# cell.net
KiCad netlist of a schematic drawn in EAGLE
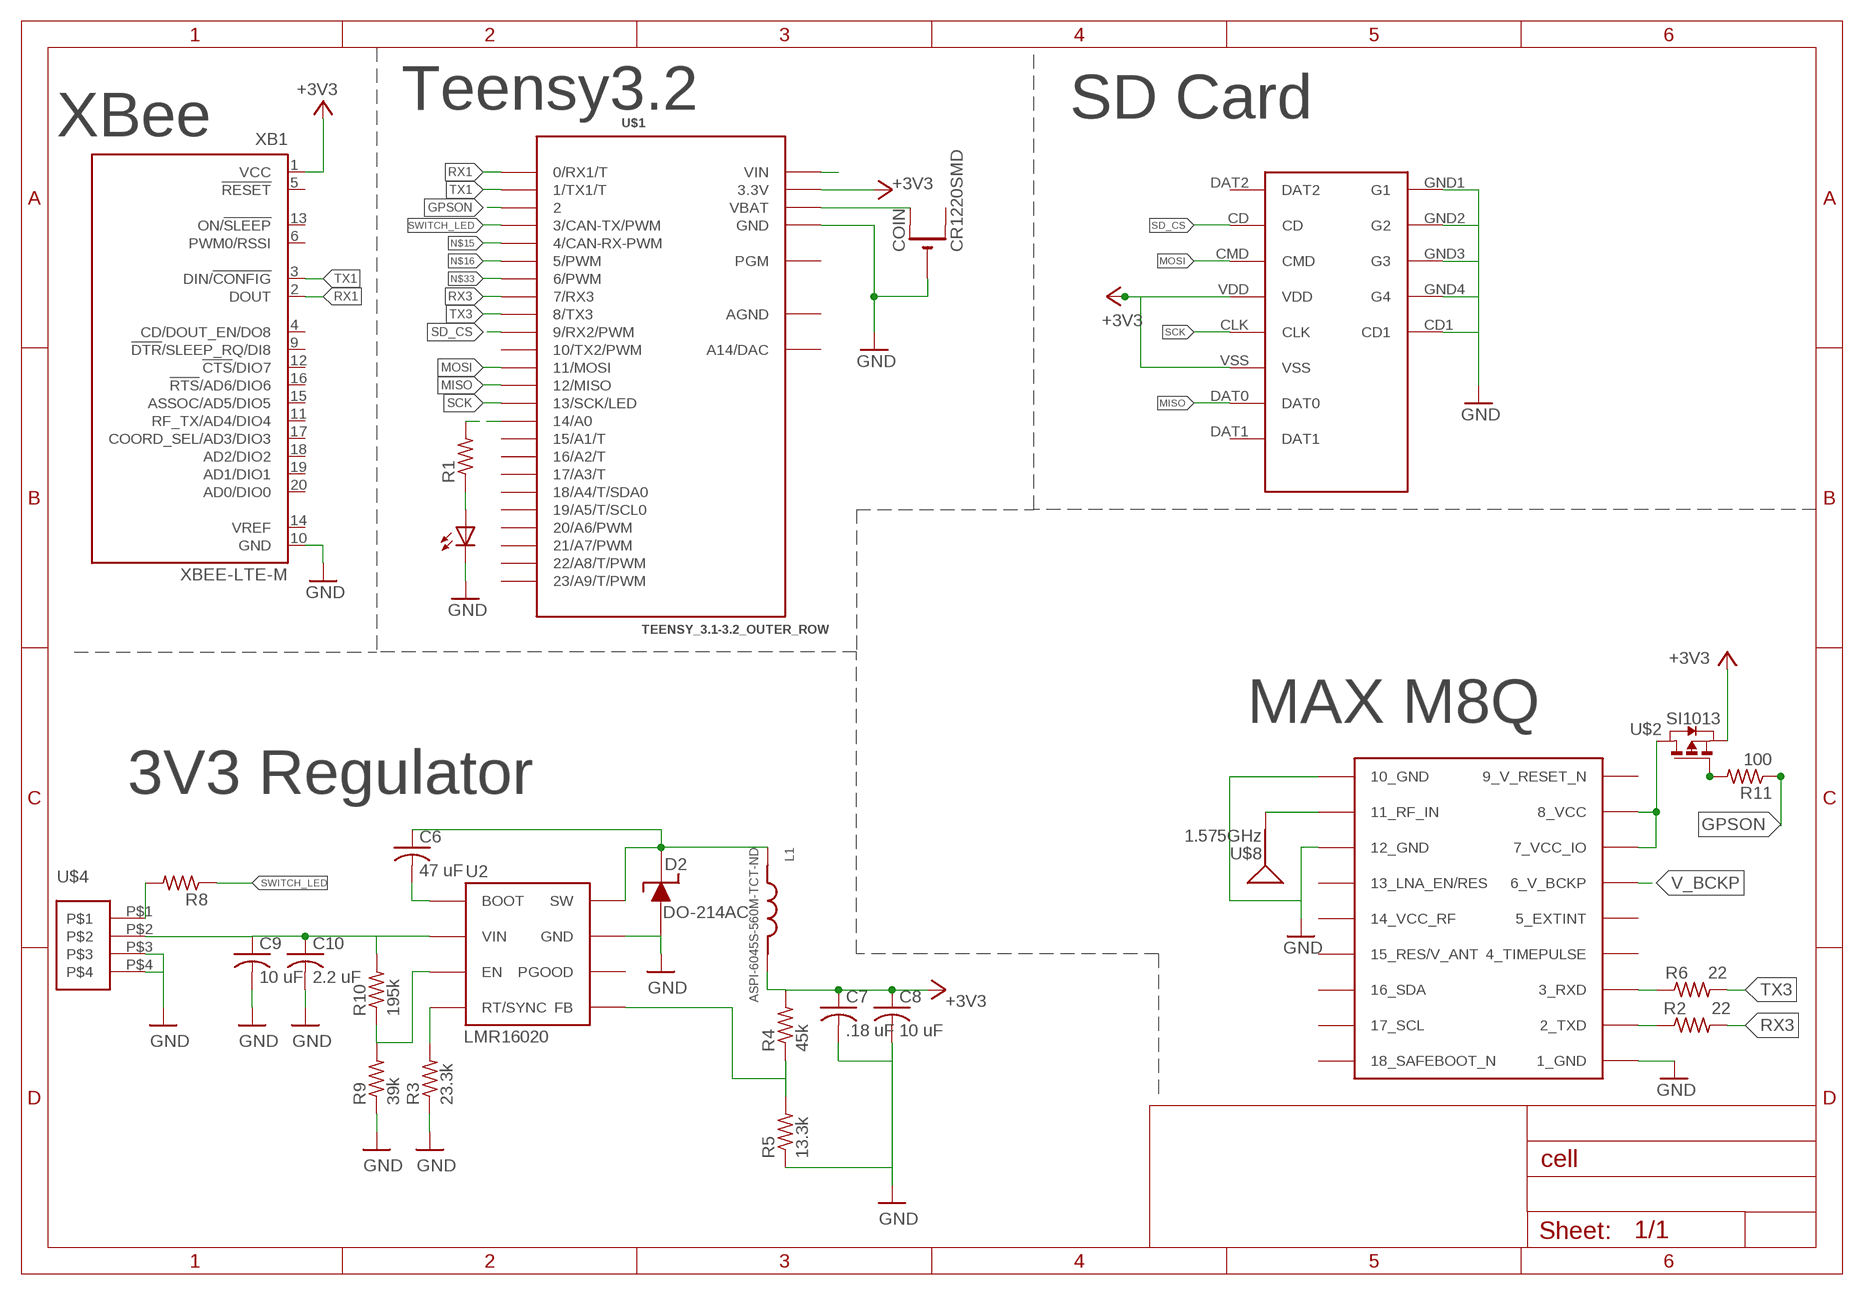
[diagram p0: schematic, sheet 1]

(export (version "E")
  (design (tool "Eeschema 10.0.6"))
  (components
    (comp (ref "C6")
      (value "47 uF")
      (footprint "eagle-import:C0805")
      (libsource (lib "eagle-import") (part "C-USC0805"))
    )
    (comp (ref "C7")
      (value ".18 uF")
      (footprint "eagle-import:C0603")
      (libsource (lib "eagle-import") (part "C-USC0603"))
    )
    (comp (ref "C8")
      (value "10 uF")
      (footprint "eagle-import:C0603")
      (libsource (lib "eagle-import") (part "C-USC0603"))
    )
    (comp (ref "C9")
      (value "10 uF")
      (footprint "eagle-import:C1210")
      (libsource (lib "eagle-import") (part "C-USC1210"))
    )
    (comp (ref "C10")
      (value "2.2 uF")
      (footprint "eagle-import:C1210")
      (libsource (lib "eagle-import") (part "C-USC1210"))
    )
    (comp (ref "COIN")
      (value "CR1220SMD")
      (footprint "eagle-import:CR1220-SMD")
      (libsource (lib "eagle-import") (part "CR1220SMT"))
    )
    (comp (ref "D2")
      (value "DO-214AC")
      (footprint "eagle-import:DO-214AC")
      (libsource (lib "eagle-import") (part "DO-214AC"))
    )
    (comp (ref "L1")
      (value "ASPI-6045S-560M-TCT-ND")
      (footprint "eagle-import:ABRACON")
      (libsource (lib "eagle-import") (part "ASPI-6045S-560M-TCT-ND"))
    )
    (comp (ref "LED1")
      (value "Green")
      (footprint "eagle-import:CHIP-LED0603")
      (libsource (lib "eagle-import") (part "LEDCHIP-LED0603"))
    )
    (comp (ref "R1")
      (value "470")
      (footprint "eagle-import:R0603")
      (libsource (lib "eagle-import") (part "resistor_R-US_R0603"))
    )
    (comp (ref "R2")
      (value "22")
      (footprint "eagle-import:R0603")
      (libsource (lib "eagle-import") (part "R-US_R0603"))
    )
    (comp (ref "R3")
      (value "23.3k")
      (footprint "eagle-import:R0603")
      (libsource (lib "eagle-import") (part "resistor_R-US_R0603"))
    )
    (comp (ref "R4")
      (value "45k")
      (footprint "eagle-import:R0603")
      (libsource (lib "eagle-import") (part "resistor_R-US_R0603"))
    )
    (comp (ref "R5")
      (value "13.3k")
      (footprint "eagle-import:R0603")
      (libsource (lib "eagle-import") (part "resistor_R-US_R0603"))
    )
    (comp (ref "R6")
      (value "22")
      (footprint "eagle-import:R0603")
      (libsource (lib "eagle-import") (part "R-US_R0603"))
    )
    (comp (ref "R8")
      (value "R-US_R0603")
      (footprint "eagle-import:R0603")
      (libsource (lib "eagle-import") (part "resistor_R-US_R0603"))
    )
    (comp (ref "R9")
      (value "39k")
      (footprint "eagle-import:R0603")
      (libsource (lib "eagle-import") (part "resistor_R-US_R0603"))
    )
    (comp (ref "R10")
      (value "195k")
      (footprint "eagle-import:R0603")
      (libsource (lib "eagle-import") (part "resistor_R-US_R0603"))
    )
    (comp (ref "R11")
      (value "100")
      (footprint "eagle-import:R0603")
      (libsource (lib "eagle-import") (part "R-US_R0603"))
    )
    (comp (ref "U$1")
      (value "TEENSY_3.1-3.2_OUTER_ROW")
      (footprint "eagle-import:TEENSY_3.0-3.2&LC_OUTER_ROW")
      (libsource (lib "eagle-import") (part "TEENSY_3.1-3.2_OUTER_ROW"))
    )
    (comp (ref "U$2")
      (value "SI1013")
      (footprint "eagle-import:SC-75")
      (libsource (lib "eagle-import") (part "SI1013"))
    )
    (comp (ref "U$3")
      (value "MICRO_SD")
      (footprint "eagle-import:MICRO_SD_HINGED")
      (libsource (lib "eagle-import") (part "MICRO_SD"))
    )
    (comp (ref "U$4")
      (value "MICROCLASP_4")
      (footprint "eagle-import:4_PIN_MICROCLASP")
      (libsource (lib "eagle-import") (part "MICROCLASP_4"))
    )
    (comp (ref "U$7")
      (value "MAX-M8")
      (footprint "eagle-import:MAX-M8")
      (libsource (lib "eagle-import") (part "MAX-M8"))
    )
    (comp (ref "U$8")
      (value "1.575GHz")
      (footprint "eagle-import:SPARKFUN-GPS_ANT-GPS-2X7MM")
      (libsource (lib "eagle-import") (part "SPARKFUN-GPS_ANTENNAGPS-2X7MM"))
    )
    (comp (ref "U2")
      (value "LMR16020")
      (footprint "eagle-import:SO8")
      (libsource (lib "eagle-import") (part "LMR16020"))
    )
    (comp (ref "XB1")
      (value "XBEE-LTE-M")
      (footprint "eagle-import:XBEE-PRO")
      (fields (field (name "MPN") "XBP24-AWI-001"))
      (libsource (lib "eagle-import") (part "XBEE-PRO"))
    )
  )
  (nets
    (net (code "1") (name "+3V3") (class "Default")
      (node (ref "C7") (pin "1") (pinfunction "1_1") (pintype "passive"))
      (node (ref "C8") (pin "1") (pinfunction "1_1") (pintype "passive"))
      (node (ref "L1") (pin "P$2") (pinfunction "P$2_P$2") (pintype "bidirectional"))
      (node (ref "R4") (pin "2") (pinfunction "2_2") (pintype "passive"))
      (node (ref "U$1") (pin "3.3V") (pinfunction "3.3V_3.3V") (pintype "power_in"))
      (node (ref "U$1") (pin "3.3V1") (pinfunction "3.3V_3.3V1") (pintype "power_in"))
      (node (ref "U$2") (pin "P$2") (pinfunction "S_P$2") (pintype "passive"))
      (node (ref "U$3") (pin "VDD") (pinfunction "VDD_VDD") (pintype "bidirectional"))
      (node (ref "U$3") (pin "VSS") (pinfunction "VSS_VSS") (pintype "bidirectional"))
      (node (ref "XB1") (pin "1") (pinfunction "VCC_1") (pintype "power_in"))
    )
    (net (code "2") (name "/9_V_RESET_N") (class "Default")
      (node (ref "U$7") (pin "9_RESET_N") (pinfunction "9_V_RESET_N_9_RESET_N") (pintype "power_in"))
    )
    (net (code "3") (name "/AGND") (class "Default")
      (node (ref "U$1") (pin "AGND") (pinfunction "AGND_AGND") (pintype "power_in"))
    )
    (net (code "4") (name "GND") (class "Default")
      (node (ref "C10") (pin "2") (pinfunction "2_2") (pintype "passive"))
      (node (ref "C7") (pin "2") (pinfunction "2_2") (pintype "passive"))
      (node (ref "C8") (pin "2") (pinfunction "2_2") (pintype "passive"))
      (node (ref "C9") (pin "2") (pinfunction "2_2") (pintype "passive"))
      (node (ref "COIN") (pin "-") (pinfunction "-_-") (pintype "passive"))
      (node (ref "D2") (pin "P$1") (pinfunction "P$1_P$1") (pintype "bidirectional"))
      (node (ref "LED1") (pin "C") (pinfunction "C_C") (pintype "passive"))
      (node (ref "R3") (pin "1") (pinfunction "1_1") (pintype "passive"))
      (node (ref "R5") (pin "1") (pinfunction "1_1") (pintype "passive"))
      (node (ref "R9") (pin "1") (pinfunction "1_1") (pintype "passive"))
      (node (ref "U$1") (pin "GND") (pinfunction "GND_GND") (pintype "power_in"))
      (node (ref "U$1") (pin "GND1") (pinfunction "GND_GND1") (pintype "power_in"))
      (node (ref "U$3") (pin "CD1") (pinfunction "CD1_CD1") (pintype "bidirectional"))
      (node (ref "U$3") (pin "GND1") (pinfunction "G1_GND1") (pintype "bidirectional"))
      (node (ref "U$3") (pin "GND2") (pinfunction "G2_GND2") (pintype "bidirectional"))
      (node (ref "U$3") (pin "GND3") (pinfunction "G3_GND3") (pintype "bidirectional"))
      (node (ref "U$3") (pin "GND4") (pinfunction "G4_GND4") (pintype "bidirectional"))
      (node (ref "U$4") (pin "P$3") (pinfunction "P$3_P$3") (pintype "bidirectional"))
      (node (ref "U$4") (pin "P$4") (pinfunction "P$4_P$4") (pintype "bidirectional"))
      (node (ref "U$7") (pin "10_GND") (pinfunction "10_GND_10_GND") (pintype "power_in"))
      (node (ref "U$7") (pin "12_GND") (pinfunction "12_GND_12_GND") (pintype "power_in"))
      (node (ref "U$7") (pin "1_GND") (pinfunction "1_GND_1_GND") (pintype "power_in"))
      (node (ref "U2") (pin "P$7") (pinfunction "GND_P$7") (pintype "bidirectional"))
      (node (ref "U2") (pin "PAD") (pinfunction "GND_PAD") (pintype "bidirectional"))
      (node (ref "XB1") (pin "10") (pinfunction "GND_10") (pintype "power_in"))
    )
    (net (code "5") (name "GPSON") (class "Default")
      (node (ref "R11") (pin "1") (pinfunction "1_1") (pintype "passive"))
      (node (ref "U$1") (pin "2") (pinfunction "2_2") (pintype "bidirectional"))
    )
    (net (code "6") (name "MISO") (class "Default")
      (node (ref "U$1") (pin "12") (pinfunction "12/MISO_12") (pintype "bidirectional"))
      (node (ref "U$3") (pin "DAT0") (pinfunction "DAT0_DAT0") (pintype "bidirectional"))
    )
    (net (code "7") (name "MOSI") (class "Default")
      (node (ref "U$1") (pin "11") (pinfunction "11/MOSI_11") (pintype "bidirectional"))
      (node (ref "U$3") (pin "CMD") (pinfunction "CMD_CMD") (pintype "bidirectional"))
    )
    (net (code "8") (name "N$15") (class "Default")
      (node (ref "U$1") (pin "4") (pinfunction "4/CAN-RX-PWM_4") (pintype "bidirectional"))
    )
    (net (code "9") (name "N$16") (class "Default")
      (node (ref "U$1") (pin "5") (pinfunction "5/PWM_5") (pintype "bidirectional"))
    )
    (net (code "10") (name "N$33") (class "Default")
      (node (ref "U$1") (pin "6") (pinfunction "6/PWM_6") (pintype "bidirectional"))
    )
    (net (code "11") (name "Net-(LED1-PadA)") (class "Default")
      (node (ref "LED1") (pin "A") (pinfunction "A_A") (pintype "passive"))
      (node (ref "R1") (pin "1") (pinfunction "1_1") (pintype "passive"))
    )
    (net (code "12") (name "Net-(R1-Pad2)") (class "Default")
      (node (ref "R1") (pin "2") (pinfunction "2_2") (pintype "passive"))
      (node (ref "U$1") (pin "14/A0") (pinfunction "14/A0_14/A0") (pintype "bidirectional"))
    )
    (net (code "13") (name "Net-(R2-Pad1)") (class "Default")
      (node (ref "R2") (pin "1") (pinfunction "1_1") (pintype "passive"))
      (node (ref "U$7") (pin "2_TXD") (pinfunction "2_TXD_2_TXD") (pintype "bidirectional"))
    )
    (net (code "14") (name "Net-(R6-Pad1)") (class "Default")
      (node (ref "R6") (pin "1") (pinfunction "1_1") (pintype "passive"))
      (node (ref "U$7") (pin "3_RXD") (pinfunction "3_RXD_3_RXD") (pintype "bidirectional"))
    )
    (net (code "15") (name "Net-(R8-Pad2)") (class "Default")
      (node (ref "R8") (pin "2") (pinfunction "2_2") (pintype "passive"))
      (node (ref "U$4") (pin "P$1") (pinfunction "P$1_P$1") (pintype "bidirectional"))
    )
    (net (code "16") (name "Net-(U$2-D)") (class "Default")
      (node (ref "U$2") (pin "P$3") (pinfunction "D_P$3") (pintype "passive"))
      (node (ref "U$7") (pin "7_VCC_IO") (pinfunction "7_VCC_IO_7_VCC_IO") (pintype "power_in"))
      (node (ref "U$7") (pin "8_VCC") (pinfunction "8_VCC_8_VCC") (pintype "power_in"))
    )
    (net (code "17") (name "Net-(U$2-G)") (class "Default")
      (node (ref "R11") (pin "2") (pinfunction "2_2") (pintype "passive"))
      (node (ref "U$2") (pin "P$1") (pinfunction "G_P$1") (pintype "passive"))
    )
    (net (code "18") (name "Net-(U$8-SIGNAL)") (class "Default")
      (node (ref "U$7") (pin "11_RF_IN") (pinfunction "11_RF_IN_11_RF_IN") (pintype "bidirectional"))
      (node (ref "U$8") (pin "1") (pinfunction "SIGNAL_1") (pintype "bidirectional"))
    )
    (net (code "19") (name "Net-(U2-BOOT)") (class "Default")
      (node (ref "C6") (pin "2") (pinfunction "2_2") (pintype "passive"))
      (node (ref "U2") (pin "P$1") (pinfunction "BOOT_P$1") (pintype "bidirectional"))
    )
    (net (code "20") (name "Net-(U2-EN)") (class "Default")
      (node (ref "R10") (pin "1") (pinfunction "1_1") (pintype "passive"))
      (node (ref "R9") (pin "2") (pinfunction "2_2") (pintype "passive"))
      (node (ref "U2") (pin "P$3") (pinfunction "EN_P$3") (pintype "bidirectional"))
    )
    (net (code "21") (name "Net-(U2-FB)") (class "Default")
      (node (ref "R4") (pin "1") (pinfunction "1_1") (pintype "passive"))
      (node (ref "R5") (pin "2") (pinfunction "2_2") (pintype "passive"))
      (node (ref "U2") (pin "P$5") (pinfunction "FB_P$5") (pintype "bidirectional"))
    )
    (net (code "22") (name "Net-(U2-RT{slash}SYNC)") (class "Default")
      (node (ref "R3") (pin "2") (pinfunction "2_2") (pintype "passive"))
      (node (ref "U2") (pin "P$4") (pinfunction "RT/SYNC_P$4") (pintype "bidirectional"))
    )
    (net (code "23") (name "Net-(U2-SW)") (class "Default")
      (node (ref "C6") (pin "1") (pinfunction "1_1") (pintype "passive"))
      (node (ref "D2") (pin "P$2") (pinfunction "P$2_P$2") (pintype "bidirectional"))
      (node (ref "L1") (pin "P$1") (pinfunction "P$1_P$1") (pintype "bidirectional"))
      (node (ref "U2") (pin "P$8") (pinfunction "SW_P$8") (pintype "bidirectional"))
    )
    (net (code "24") (name "Net-(U2-VIN)") (class "Default")
      (node (ref "C10") (pin "1") (pinfunction "1_1") (pintype "passive"))
      (node (ref "C9") (pin "1") (pinfunction "1_1") (pintype "passive"))
      (node (ref "R10") (pin "2") (pinfunction "2_2") (pintype "passive"))
      (node (ref "U$4") (pin "P$2") (pinfunction "P$2_P$2") (pintype "bidirectional"))
      (node (ref "U2") (pin "P$2") (pinfunction "VIN_P$2") (pintype "bidirectional"))
    )
    (net (code "25") (name "RX1") (class "Default")
      (node (ref "U$1") (pin "0") (pinfunction "0/RX1/T_0") (pintype "bidirectional"))
      (node (ref "XB1") (pin "2") (pinfunction "DOUT_2") (pintype "output"))
    )
    (net (code "26") (name "RX3") (class "Default")
      (node (ref "R2") (pin "2") (pinfunction "2_2") (pintype "passive"))
      (node (ref "U$1") (pin "7") (pinfunction "7/RX3_7") (pintype "bidirectional"))
    )
    (net (code "27") (name "SCK") (class "Default")
      (node (ref "U$1") (pin "13") (pinfunction "13/SCK/LED_13") (pintype "bidirectional"))
      (node (ref "U$3") (pin "CLK") (pinfunction "CLK_CLK") (pintype "bidirectional"))
    )
    (net (code "28") (name "SD_CS") (class "Default")
      (node (ref "U$1") (pin "9") (pinfunction "9/RX2/PWM_9") (pintype "bidirectional"))
      (node (ref "U$3") (pin "CD") (pinfunction "CD_CD") (pintype "bidirectional"))
    )
    (net (code "29") (name "SWITCH_LED") (class "Default")
      (node (ref "R8") (pin "1") (pinfunction "1_1") (pintype "passive"))
      (node (ref "U$1") (pin "3") (pinfunction "3/CAN-TX/PWM_3") (pintype "bidirectional"))
    )
    (net (code "30") (name "TX1") (class "Default")
      (node (ref "U$1") (pin "1") (pinfunction "1/TX1/T_1") (pintype "bidirectional"))
      (node (ref "XB1") (pin "3") (pinfunction "DIN/~{CONFIG}_3") (pintype "input"))
    )
    (net (code "31") (name "TX3") (class "Default")
      (node (ref "R6") (pin "2") (pinfunction "2_2") (pintype "passive"))
      (node (ref "U$1") (pin "8") (pinfunction "8/TX3_8") (pintype "bidirectional"))
    )
    (net (code "32") (name "V_BCKP") (class "Default")
      (node (ref "COIN") (pin "+$1") (pinfunction "+_+$1") (pintype "passive"))
      (node (ref "U$1") (pin "VBAT") (pinfunction "VBAT_VBAT") (pintype "power_in"))
      (node (ref "U$7") (pin "6_V_BCKP") (pinfunction "6_V_BCKP_6_V_BCKP") (pintype "bidirectional"))
    )
    (net (code "33") (name "unconnected-(COIN-+1-Pad+$2)") (class "Default")
      (node (ref "COIN") (pin "+$2") (pinfunction "+1_+$2") (pintype "passive"))
    )
    (net (code "34") (name "unconnected-(U$1-10{slash}TX2{slash}PWM-Pad10)") (class "Default")
      (node (ref "U$1") (pin "10") (pinfunction "10/TX2/PWM_10") (pintype "bidirectional"))
    )
    (net (code "35") (name "unconnected-(U$1-15{slash}A1{slash}T-Pad15{slash}A1)") (class "Default")
      (node (ref "U$1") (pin "15/A1") (pinfunction "15/A1/T_15/A1") (pintype "bidirectional"))
    )
    (net (code "36") (name "unconnected-(U$1-16{slash}A2{slash}T-Pad16{slash}A2)") (class "Default")
      (node (ref "U$1") (pin "16/A2") (pinfunction "16/A2/T_16/A2") (pintype "bidirectional"))
    )
    (net (code "37") (name "unconnected-(U$1-17{slash}A3{slash}T-Pad17{slash}A3)") (class "Default")
      (node (ref "U$1") (pin "17/A3") (pinfunction "17/A3/T_17/A3") (pintype "bidirectional"))
    )
    (net (code "38") (name "unconnected-(U$1-18{slash}A4{slash}T{slash}SDA0-Pad18{slash}A4)") (class "Default")
      (node (ref "U$1") (pin "18/A4") (pinfunction "18/A4/T/SDA0_18/A4") (pintype "bidirectional"))
    )
    (net (code "39") (name "unconnected-(U$1-19{slash}A5{slash}T{slash}SCL0-Pad19{slash}A5)") (class "Default")
      (node (ref "U$1") (pin "19/A5") (pinfunction "19/A5/T/SCL0_19/A5") (pintype "bidirectional"))
    )
    (net (code "40") (name "unconnected-(U$1-20{slash}A6{slash}PWM-Pad20{slash}A6)") (class "Default")
      (node (ref "U$1") (pin "20/A6") (pinfunction "20/A6/PWM_20/A6") (pintype "bidirectional"))
    )
    (net (code "41") (name "unconnected-(U$1-21{slash}A7{slash}PWM-Pad21{slash}A7)") (class "Default")
      (node (ref "U$1") (pin "21/A7") (pinfunction "21/A7/PWM_21/A7") (pintype "bidirectional"))
    )
    (net (code "42") (name "unconnected-(U$1-22{slash}A8{slash}T{slash}PWM-Pad22{slash}A8)") (class "Default")
      (node (ref "U$1") (pin "22/A8") (pinfunction "22/A8/T/PWM_22/A8") (pintype "bidirectional"))
    )
    (net (code "43") (name "unconnected-(U$1-23{slash}A9{slash}T{slash}PWM-Pad23{slash}A9)") (class "Default")
      (node (ref "U$1") (pin "23/A9") (pinfunction "23/A9/T/PWM_23/A9") (pintype "bidirectional"))
    )
    (net (code "44") (name "unconnected-(U$1-A14{slash}DAC-PadRESET{slash}DAC)") (class "Default")
      (node (ref "U$1") (pin "RESET/DAC") (pinfunction "A14/DAC_RESET/DAC") (pintype "bidirectional"))
    )
    (net (code "45") (name "unconnected-(U$1-PadPGM)") (class "Default")
      (node (ref "U$1") (pin "PGM") (pinfunction "PGM_PGM") (pintype "bidirectional"))
    )
    (net (code "46") (name "unconnected-(U$1-PadVIN)") (class "Default")
      (node (ref "U$1") (pin "VIN") (pinfunction "VIN_VIN") (pintype "power_in"))
    )
    (net (code "47") (name "unconnected-(U$3-PadDAT1)") (class "Default")
      (node (ref "U$3") (pin "DAT1") (pinfunction "DAT1_DAT1") (pintype "bidirectional"))
    )
    (net (code "48") (name "unconnected-(U$3-PadDAT2)") (class "Default")
      (node (ref "U$3") (pin "DAT2") (pinfunction "DAT2_DAT2") (pintype "bidirectional"))
    )
    (net (code "49") (name "unconnected-(U$7-13_LNA_EN{slash}RES-Pad13_LNA_EN)") (class "Default")
      (node (ref "U$7") (pin "13_LNA_EN") (pinfunction "13_LNA_EN/RES_13_LNA_EN") (pintype "bidirectional"))
    )
    (net (code "50") (name "unconnected-(U$7-15_RES{slash}V_ANT-Pad15_V_ANT{slash}RESERVED)") (class "Default")
      (node (ref "U$7") (pin "15_V_ANT/RESERVED") (pinfunction "15_RES/V_ANT_15_V_ANT/RESERVED") (pintype "bidirectional"))
    )
    (net (code "51") (name "unconnected-(U$7-Pad4_TIMEPULSE)") (class "Default")
      (node (ref "U$7") (pin "4_TIMEPULSE") (pinfunction "4_TIMEPULSE_4_TIMEPULSE") (pintype "bidirectional"))
    )
    (net (code "52") (name "unconnected-(U$7-Pad5_EXTINT)") (class "Default")
      (node (ref "U$7") (pin "5_EXTINT") (pinfunction "5_EXTINT_5_EXTINT") (pintype "bidirectional"))
    )
    (net (code "53") (name "unconnected-(U$7-Pad14_VCC_RF)") (class "Default")
      (node (ref "U$7") (pin "14_VCC_RF") (pinfunction "14_VCC_RF_14_VCC_RF") (pintype "bidirectional"))
    )
    (net (code "54") (name "unconnected-(U$7-Pad16_SDA)") (class "Default")
      (node (ref "U$7") (pin "16_SDA") (pinfunction "16_SDA_16_SDA") (pintype "bidirectional"))
    )
    (net (code "55") (name "unconnected-(U$7-Pad17_SCL)") (class "Default")
      (node (ref "U$7") (pin "17_SCL") (pinfunction "17_SCL_17_SCL") (pintype "bidirectional"))
    )
    (net (code "56") (name "unconnected-(U$7-Pad18_SAFEBOOT_N)") (class "Default")
      (node (ref "U$7") (pin "18_SAFEBOOT_N") (pinfunction "18_SAFEBOOT_N_18_SAFEBOOT_N") (pintype "bidirectional"))
    )
    (net (code "57") (name "unconnected-(U2-PGOOD-PadP$6)") (class "Default")
      (node (ref "U2") (pin "P$6") (pinfunction "PGOOD_P$6") (pintype "bidirectional"))
    )
    (net (code "58") (name "unconnected-(XB1-AD0{slash}DIO0-Pad20)") (class "Default")
      (node (ref "XB1") (pin "20") (pinfunction "AD0/DIO0_20") (pintype "bidirectional"))
    )
    (net (code "59") (name "unconnected-(XB1-AD1{slash}DIO1-Pad19)") (class "Default")
      (node (ref "XB1") (pin "19") (pinfunction "AD1/DIO1_19") (pintype "bidirectional"))
    )
    (net (code "60") (name "unconnected-(XB1-AD2{slash}DIO2-Pad18)") (class "Default")
      (node (ref "XB1") (pin "18") (pinfunction "AD2/DIO2_18") (pintype "bidirectional"))
    )
    (net (code "61") (name "unconnected-(XB1-ASSOC{slash}AD5{slash}DIO5-Pad15)") (class "Default")
      (node (ref "XB1") (pin "15") (pinfunction "ASSOC/AD5/DIO5_15") (pintype "bidirectional"))
    )
    (net (code "62") (name "unconnected-(XB1-CD{slash}DOUT_EN{slash}DO8-Pad4)") (class "Default")
      (node (ref "XB1") (pin "4") (pinfunction "CD/DOUT_EN/DO8_4") (pintype "output"))
    )
    (net (code "63") (name "unconnected-(XB1-COORD_SEL{slash}AD3{slash}DIO3-Pad17)") (class "Default")
      (node (ref "XB1") (pin "17") (pinfunction "COORD_SEL/AD3/DIO3_17") (pintype "bidirectional"))
    )
    (net (code "64") (name "unconnected-(XB1-ON{slash}~{SLEEP}-Pad13)") (class "Default")
      (node (ref "XB1") (pin "13") (pinfunction "ON/~{SLEEP}_13") (pintype "output"))
    )
    (net (code "65") (name "unconnected-(XB1-PWM0{slash}RSSI-Pad6)") (class "Default")
      (node (ref "XB1") (pin "6") (pinfunction "PWM0/RSSI_6") (pintype "output"))
    )
    (net (code "66") (name "unconnected-(XB1-RF_TX{slash}AD4{slash}DIO4-Pad11)") (class "Default")
      (node (ref "XB1") (pin "11") (pinfunction "RF_TX/AD4/DIO4_11") (pintype "bidirectional"))
    )
    (net (code "67") (name "unconnected-(XB1-VREF-Pad14)") (class "Default")
      (node (ref "XB1") (pin "14") (pinfunction "VREF_14") (pintype "input"))
    )
    (net (code "68") (name "unconnected-(XB1-~{CTS}{slash}DIO7-Pad12)") (class "Default")
      (node (ref "XB1") (pin "12") (pinfunction "~{CTS}/DIO7_12") (pintype "bidirectional"))
    )
    (net (code "69") (name "unconnected-(XB1-~{DTR}{slash}SLEEP_RQ{slash}DI8-Pad9)") (class "Default")
      (node (ref "XB1") (pin "9") (pinfunction "~{DTR}/SLEEP_RQ/DI8_9") (pintype "bidirectional"))
    )
    (net (code "70") (name "unconnected-(XB1-~{RESET}-Pad5)") (class "Default")
      (node (ref "XB1") (pin "5") (pinfunction "~{RESET}_5") (pintype "input"))
    )
    (net (code "71") (name "unconnected-(XB1-~{RTS}{slash}AD6{slash}DIO6-Pad16)") (class "Default")
      (node (ref "XB1") (pin "16") (pinfunction "~{RTS}/AD6/DIO6_16") (pintype "bidirectional"))
    )
  )
)
